# Interface_MCU.net
KiCad netlist of a schematic drawn in Altium Designer
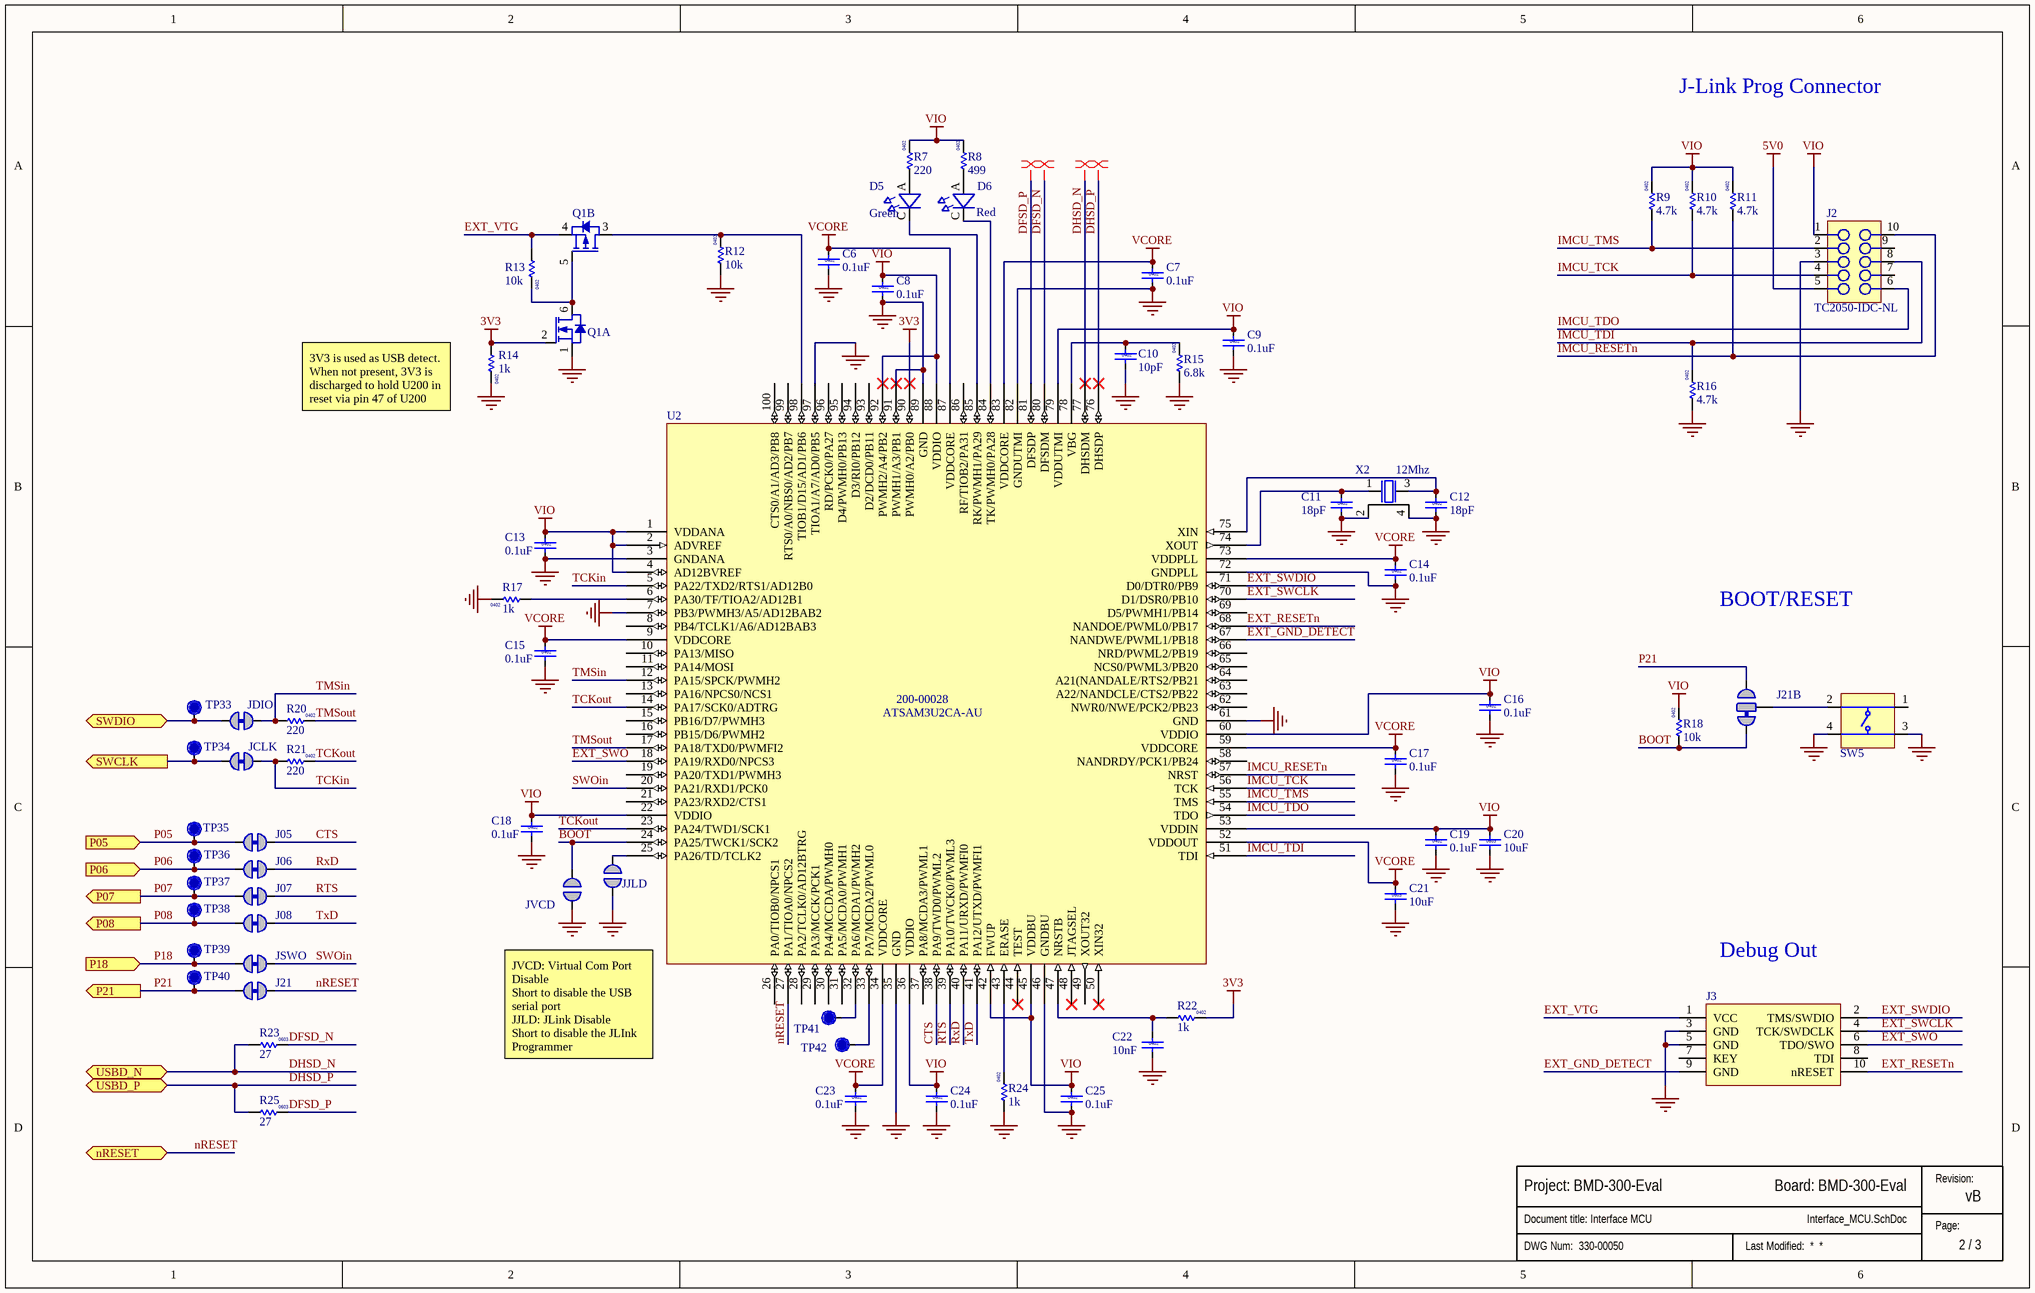
[diagram p0: Interface_MCU.SchDoc]

(export (version "E")
  (design (tool "Eeschema 10.0.6"))
  (components
    (comp (ref "C6")
      (value "0.1uF")
      (footprint "Cap 0402 HD")
      (description "Cap, Ceramic 0.1uF 10V 10% X5R 0402")
      (fields
        (field (name "SIZE") "0402")
        (field (name "PART NUMBER") "120-00016")
        (field (name "MANUFACTURER") "Murata Electronics North America")
      )
      (libsource (lib "Arena-Altium DB") (part "Cap Chip"))
    )
    (comp (ref "C7")
      (value "0.1uF")
      (footprint "Cap 0402 HD")
      (description "Cap, Ceramic 0.1uF 10V 10% X5R 0402")
      (fields
        (field (name "SIZE") "0402")
        (field (name "PART NUMBER") "120-00016")
        (field (name "MANUFACTURER") "Murata Electronics North America")
      )
      (libsource (lib "Arena-Altium DB") (part "Cap Chip"))
    )
    (comp (ref "C8")
      (value "0.1uF")
      (footprint "Cap 0402 HD")
      (description "Cap, Ceramic 0.1uF 10V 10% X5R 0402")
      (fields
        (field (name "SIZE") "0402")
        (field (name "PART NUMBER") "120-00016")
        (field (name "MANUFACTURER") "Murata Electronics North America")
      )
      (libsource (lib "Arena-Altium DB") (part "Cap Chip"))
    )
    (comp (ref "C9")
      (value "0.1uF")
      (footprint "Cap 0402 HD")
      (description "Cap, Ceramic 0.1uF 10V 10% X5R 0402")
      (fields
        (field (name "SIZE") "0402")
        (field (name "PART NUMBER") "120-00016")
        (field (name "MANUFACTURER") "Murata Electronics North America")
      )
      (libsource (lib "Arena-Altium DB") (part "Cap Chip"))
    )
    (comp (ref "C10")
      (value "10pF")
      (footprint "Cap 0402")
      (description "Cap, Ceramic, 10pF 50V 5% NPO 0402")
      (fields
        (field (name "SIZE") "0402")
        (field (name "PART NUMBER") "120-00065")
        (field (name "MANUFACTURER") "Murata Electronics North America")
      )
      (libsource (lib "Arena-Altium DB") (part "Cap Chip"))
    )
    (comp (ref "C11")
      (value "18pF")
      (footprint "Cap 0402 HD")
      (description "Cap, Ceramic 18pF 50V 5% NP0 0402")
      (fields
        (field (name "SIZE") "0402")
        (field (name "PART NUMBER") "120-00041")
        (field (name "MANUFACTURER") "Murata Electronics North America")
      )
      (libsource (lib "Arena-Altium DB") (part "Cap Chip"))
    )
    (comp (ref "C12")
      (value "18pF")
      (footprint "Cap 0402 HD")
      (description "Cap, Ceramic 18pF 50V 5% NP0 0402")
      (fields
        (field (name "SIZE") "0402")
        (field (name "PART NUMBER") "120-00041")
        (field (name "MANUFACTURER") "Murata Electronics North America")
      )
      (libsource (lib "Arena-Altium DB") (part "Cap Chip"))
    )
    (comp (ref "C13")
      (value "0.1uF")
      (footprint "Cap 0402 HD")
      (description "Cap, Ceramic 0.1uF 10V 10% X5R 0402")
      (fields
        (field (name "SIZE") "0402")
        (field (name "PART NUMBER") "120-00016")
        (field (name "MANUFACTURER") "Murata Electronics North America")
      )
      (libsource (lib "Arena-Altium DB") (part "Cap Chip"))
    )
    (comp (ref "C14")
      (value "0.1uF")
      (footprint "Cap 0402 HD")
      (description "Cap, Ceramic 0.1uF 10V 10% X5R 0402")
      (fields
        (field (name "SIZE") "0402")
        (field (name "PART NUMBER") "120-00016")
        (field (name "MANUFACTURER") "Murata Electronics North America")
      )
      (libsource (lib "Arena-Altium DB") (part "Cap Chip"))
    )
    (comp (ref "C15")
      (value "0.1uF")
      (footprint "Cap 0402 HD")
      (description "Cap, Ceramic 0.1uF 10V 10% X5R 0402")
      (fields
        (field (name "SIZE") "0402")
        (field (name "PART NUMBER") "120-00016")
        (field (name "MANUFACTURER") "Murata Electronics North America")
      )
      (libsource (lib "Arena-Altium DB") (part "Cap Chip"))
    )
    (comp (ref "C16")
      (value "0.1uF")
      (footprint "Cap 0402 HD")
      (description "Cap, Ceramic 0.1uF 10V 10% X5R 0402")
      (fields
        (field (name "SIZE") "0402")
        (field (name "PART NUMBER") "120-00016")
        (field (name "MANUFACTURER") "Murata Electronics North America")
      )
      (libsource (lib "Arena-Altium DB") (part "Cap Chip"))
    )
    (comp (ref "C17")
      (value "0.1uF")
      (footprint "Cap 0402 HD")
      (description "Cap, Ceramic 0.1uF 10V 10% X5R 0402")
      (fields
        (field (name "SIZE") "0402")
        (field (name "PART NUMBER") "120-00016")
        (field (name "MANUFACTURER") "Murata Electronics North America")
      )
      (libsource (lib "Arena-Altium DB") (part "Cap Chip"))
    )
    (comp (ref "C18")
      (value "0.1uF")
      (footprint "Cap 0402 HD")
      (description "Cap, Ceramic 0.1uF 10V 10% X5R 0402")
      (fields
        (field (name "SIZE") "0402")
        (field (name "PART NUMBER") "120-00016")
        (field (name "MANUFACTURER") "Murata Electronics North America")
      )
      (libsource (lib "Arena-Altium DB") (part "Cap Chip"))
    )
    (comp (ref "C19")
      (value "0.1uF")
      (footprint "Cap 0402 HD")
      (description "Cap, Ceramic 0.1uF 10V 10% X5R 0402")
      (fields
        (field (name "SIZE") "0402")
        (field (name "PART NUMBER") "120-00016")
        (field (name "MANUFACTURER") "Murata Electronics North America")
      )
      (libsource (lib "Arena-Altium DB") (part "Cap Chip"))
    )
    (comp (ref "C20")
      (value "10uF")
      (footprint "Cap 0603 HD")
      (description "Cap, Ceramic 10uF 10V 20% X5R 0603")
      (fields
        (field (name "SIZE") "0603")
        (field (name "PART NUMBER") "120-00024")
        (field (name "MANUFACTURER") "Murata Electronics North America")
      )
      (libsource (lib "Arena-Altium DB") (part "Cap Chip"))
    )
    (comp (ref "C21")
      (value "10uF")
      (footprint "Cap 0603 HD")
      (description "Cap, Ceramic 10uF 10V 20% X5R 0603")
      (fields
        (field (name "SIZE") "0603")
        (field (name "PART NUMBER") "120-00024")
        (field (name "MANUFACTURER") "Murata Electronics North America")
      )
      (libsource (lib "Arena-Altium DB") (part "Cap Chip"))
    )
    (comp (ref "C22")
      (value "10nF")
      (footprint "Cap 0402 HD")
      (description "CL05B103KO5NNNC")
      (fields
        (field (name "SIZE") "0402")
        (field (name "PART NUMBER") "120-00084")
        (field (name "MANUFACTURER") "Samsung Electro-Mechanics America, Inc")
      )
      (libsource (lib "Arena-Altium DB") (part "Cap Chip"))
    )
    (comp (ref "C23")
      (value "0.1uF")
      (footprint "Cap 0402 HD")
      (description "Cap, Ceramic 0.1uF 10V 10% X5R 0402")
      (fields
        (field (name "SIZE") "0402")
        (field (name "PART NUMBER") "120-00016")
        (field (name "MANUFACTURER") "Murata Electronics North America")
      )
      (libsource (lib "Arena-Altium DB") (part "Cap Chip"))
    )
    (comp (ref "C24")
      (value "0.1uF")
      (footprint "Cap 0402 HD")
      (description "Cap, Ceramic 0.1uF 10V 10% X5R 0402")
      (fields
        (field (name "SIZE") "0402")
        (field (name "PART NUMBER") "120-00016")
        (field (name "MANUFACTURER") "Murata Electronics North America")
      )
      (libsource (lib "Arena-Altium DB") (part "Cap Chip"))
    )
    (comp (ref "C25")
      (value "0.1uF")
      (footprint "Cap 0402 HD")
      (description "Cap, Ceramic 0.1uF 10V 10% X5R 0402")
      (fields
        (field (name "SIZE") "0402")
        (field (name "PART NUMBER") "120-00016")
        (field (name "MANUFACTURER") "Murata Electronics North America")
      )
      (libsource (lib "Arena-Altium DB") (part "Cap Chip"))
    )
    (comp (ref "D5")
      (value "115-00019")
      (footprint "Diode 0603 HD")
      (description "LED GREEN CLEAR 0603 SMD")
      (fields (field (name "COLOR") "Green") (field (name "MANUFACTURER") "Lite-On Inc"))
      (libsource (lib "Arena-Altium DB") (part "LED_BASE_AC"))
    )
    (comp (ref "D6")
      (value "115-00020")
      (footprint "Diode 0603 HD")
      (description "LED RED CLEAR 0603 SMD")
      (fields (field (name "COLOR") "Red") (field (name "MANUFACTURER") "Lite-On Inc"))
      (libsource (lib "Arena-Altium DB") (part "LED_BASE_AC"))
    )
    (comp (ref "J2")
      (value "TC2050-IDC-NLDNP")
      (footprint "TC2050-IDC-NL")
      (description "CON PADS FOR CBL PLUG-OF-NAILS 10-PIN NO LEGS")
      (fields
        (field (name "MANUFACTURER P/N") "TC2050-IDC-NL")
        (field (name "PART NUMBER") "TC2050-IDC-NL")
        (field (name "MANUFACTURER") "TAG Connect")
        (field (name "ADDED BY") "Paul B")
      )
      (libsource (lib "LEGACY_Rigado_AltiumLib") (part "CON-10Pin_2Row_ALT"))
    )
    (comp (ref "J3")
      (value "130-00099")
      (footprint "HDR.050P-10Pin-2x5-SMT_Key")
      (description "Header 0.05\" 10Pin 2Row SMD Black")
      (fields (field (name "MANUFACTURER") "Samtec"))
      (libsource (lib "Arena-Altium DB") (part "JTAG-10Pin"))
    )
    (comp (ref "J05")
      (value "Solderbridge-ShortDNP")
      (footprint "Solderbridge-Short")
      (description "Solderbridge-Short")
      (fields (field (name "ADDED BY") "Paul B"))
      (libsource (lib "LEGACY_Rigado_AltiumLib") (part "Solderbridge-Short"))
    )
    (comp (ref "J06")
      (value "Solderbridge-ShortDNP")
      (footprint "Solderbridge-Short")
      (description "Solderbridge-Short")
      (fields (field (name "ADDED BY") "Paul B"))
      (libsource (lib "LEGACY_Rigado_AltiumLib") (part "Solderbridge-Short"))
    )
    (comp (ref "J07")
      (value "Solderbridge-ShortDNP")
      (footprint "Solderbridge-Short")
      (description "Solderbridge-Short")
      (fields (field (name "ADDED BY") "Paul B"))
      (libsource (lib "LEGACY_Rigado_AltiumLib") (part "Solderbridge-Short"))
    )
    (comp (ref "J08")
      (value "Solderbridge-ShortDNP")
      (footprint "Solderbridge-Short")
      (description "Solderbridge-Short")
      (fields (field (name "ADDED BY") "Paul B"))
      (libsource (lib "LEGACY_Rigado_AltiumLib") (part "Solderbridge-Short"))
    )
    (comp (ref "J21")
      (value "Solderbridge-ShortDNP")
      (footprint "Solderbridge-Short")
      (description "Solderbridge-Short")
      (fields (field (name "ADDED BY") "Paul B"))
      (libsource (lib "LEGACY_Rigado_AltiumLib") (part "Solderbridge-Short"))
    )
    (comp (ref "J21B")
      (value "Solderbridge-OptionDNP")
      (footprint "Solderbridge-Option")
      (description "Solderbridge-Option")
      (fields (field (name "ADDED BY") "Paul B"))
      (libsource (lib "LEGACY_Rigado_AltiumLib") (part "Solderbridge-Option"))
    )
    (comp (ref "JCLK")
      (value "Solderbridge-ShortDNP")
      (footprint "Solderbridge-Short")
      (description "Solderbridge-Short")
      (fields (field (name "ADDED BY") "Paul B"))
      (libsource (lib "LEGACY_Rigado_AltiumLib") (part "Solderbridge-Short"))
    )
    (comp (ref "JDIO")
      (value "Solderbridge-ShortDNP")
      (footprint "Solderbridge-Short")
      (description "Solderbridge-Short")
      (fields (field (name "ADDED BY") "Paul B"))
      (libsource (lib "LEGACY_Rigado_AltiumLib") (part "Solderbridge-Short"))
    )
    (comp (ref "JJLD")
      (value "Solderbridge-OpenDNP")
      (footprint "Solderbridge-Open")
      (description "Solderbridge-Open")
      (fields (field (name "ADDED BY") "Paul B"))
      (libsource (lib "LEGACY_Rigado_AltiumLib") (part "Solderbridge-Open"))
    )
    (comp (ref "JSWO")
      (value "Solderbridge-ShortDNP")
      (footprint "Solderbridge-Short")
      (description "Solderbridge-Short")
      (fields (field (name "ADDED BY") "Paul B"))
      (libsource (lib "LEGACY_Rigado_AltiumLib") (part "Solderbridge-Short"))
    )
    (comp (ref "JVCD")
      (value "Solderbridge-OpenDNP")
      (footprint "Solderbridge-Open")
      (description "Solderbridge-Open")
      (fields (field (name "ADDED BY") "Paul B"))
      (libsource (lib "LEGACY_Rigado_AltiumLib") (part "Solderbridge-Open"))
    )
    (comp (ref "Q1")
      (value "140-00019")
      (footprint "SOT-963")
      (description "Mosfet, Dual, N-Channel and P-Channel Pair, 20V 180mA, SOT963")
      (fields (field (name "MANUFACTURER") "Diodes Incorporated") (field (name "VOLTAGE") "20V, -20V"))
      (libsource (lib "Arena-Altium DB") (part "MOSFET-N-P_Pair"))
    )
    (comp (ref "R7")
      (value "220")
      (footprint "RES 0402 HD")
      (description "RC1005J221CS")
      (fields
        (field (name "SIZE") "0402")
        (field (name "PART NUMBER") "180-00098")
        (field (name "MANUFACTURER") "Samsung Electro-Mechanics America, Inc")
      )
      (libsource (lib "Arena-Altium DB") (part "Res sm"))
    )
    (comp (ref "R8")
      (value "499")
      (footprint "RES 0402 HD")
      (description "Resistor 499 ohm 1%, 1/16W, 0402")
      (fields
        (field (name "SIZE") "0402")
        (field (name "PART NUMBER") "180-00031")
        (field (name "MANUFACTURER") "Rohm Semiconductor")
      )
      (libsource (lib "Arena-Altium DB") (part "Res sm"))
    )
    (comp (ref "R9")
      (value "4.7k")
      (footprint "RES 0402 HD")
      (description "RES SMD 4.7K OHM 1% 1/16W 0402")
      (fields
        (field (name "SIZE") "0402")
        (field (name "PART NUMBER") "180-00121")
        (field (name "MANUFACTURER") "Samsung Electro-Mechanics America, Inc")
      )
      (libsource (lib "Arena-Altium DB") (part "Res sm"))
    )
    (comp (ref "R10")
      (value "4.7k")
      (footprint "RES 0402 HD")
      (description "RES SMD 4.7K OHM 1% 1/16W 0402")
      (fields
        (field (name "SIZE") "0402")
        (field (name "PART NUMBER") "180-00121")
        (field (name "MANUFACTURER") "Samsung Electro-Mechanics America, Inc")
      )
      (libsource (lib "Arena-Altium DB") (part "Res sm"))
    )
    (comp (ref "R11")
      (value "4.7k")
      (footprint "RES 0402 HD")
      (description "RES SMD 4.7K OHM 1% 1/16W 0402")
      (fields
        (field (name "SIZE") "0402")
        (field (name "PART NUMBER") "180-00121")
        (field (name "MANUFACTURER") "Samsung Electro-Mechanics America, Inc")
      )
      (libsource (lib "Arena-Altium DB") (part "Res sm"))
    )
    (comp (ref "R12")
      (value "10k")
      (footprint "RES 0402 HD")
      (description "Resistor 10k ohm 1% 1/16W, 0402")
      (fields
        (field (name "SIZE") "0402")
        (field (name "PART NUMBER") "180-00024")
        (field (name "MANUFACTURER") "Rohm Semiconductor")
      )
      (libsource (lib "Arena-Altium DB") (part "Res sm"))
    )
    (comp (ref "R13")
      (value "10k")
      (footprint "RES 0402 HD")
      (description "Resistor 10k ohm 1% 1/16W, 0402")
      (fields
        (field (name "SIZE") "0402")
        (field (name "PART NUMBER") "180-00024")
        (field (name "MANUFACTURER") "Rohm Semiconductor")
      )
      (libsource (lib "Arena-Altium DB") (part "Res sm"))
    )
    (comp (ref "R14")
      (value "1k")
      (footprint "RES 0402 HD")
      (description "Resistor 1k ohm 1% 1/16W, 0402")
      (fields
        (field (name "SIZE") "0402")
        (field (name "PART NUMBER") "180-00021")
        (field (name "MANUFACTURER") "Rohm Semiconductor")
      )
      (libsource (lib "Arena-Altium DB") (part "Res sm"))
    )
    (comp (ref "R15")
      (value "6.8k")
      (footprint "RES 0402")
      (description "Resistor 6.8k ohm 1%, 1/16W, 0402")
      (fields
        (field (name "SIZE") "0402")
        (field (name "PART NUMBER") "180-00068")
        (field (name "MANUFACTURER") "Rohm Semiconductor")
      )
      (libsource (lib "Arena-Altium DB") (part "Res sm"))
    )
    (comp (ref "R16")
      (value "4.7k")
      (footprint "RES 0402 HD")
      (description "RES SMD 4.7K OHM 1% 1/16W 0402")
      (fields
        (field (name "SIZE") "0402")
        (field (name "PART NUMBER") "180-00121")
        (field (name "MANUFACTURER") "Samsung Electro-Mechanics America, Inc")
      )
      (libsource (lib "Arena-Altium DB") (part "Res sm"))
    )
    (comp (ref "R17")
      (value "1k")
      (footprint "RES 0402 HD")
      (description "Resistor 1k ohm 1% 1/16W, 0402")
      (fields
        (field (name "SIZE") "0402")
        (field (name "PART NUMBER") "180-00021")
        (field (name "MANUFACTURER") "Rohm Semiconductor")
      )
      (libsource (lib "Arena-Altium DB") (part "Res sm"))
    )
    (comp (ref "R18")
      (value "10k")
      (footprint "RES 0402 HD")
      (description "Resistor 10k ohm 1% 1/16W, 0402")
      (fields
        (field (name "SIZE") "0402")
        (field (name "PART NUMBER") "180-00024")
        (field (name "MANUFACTURER") "Rohm Semiconductor")
      )
      (libsource (lib "Arena-Altium DB") (part "Res sm"))
    )
    (comp (ref "R20")
      (value "220")
      (footprint "RES 0402 HD")
      (description "Resistor 220 ohm 1%, 1/16W, 0402")
      (fields
        (field (name "SIZE") "0402")
        (field (name "PART NUMBER") "180-00056")
        (field (name "MANUFACTURER") "Panasonic Electronic Components")
      )
      (libsource (lib "Arena-Altium DB") (part "Res sm"))
    )
    (comp (ref "R21")
      (value "220")
      (footprint "RES 0402 HD")
      (description "Resistor 220 ohm 1%, 1/16W, 0402")
      (fields
        (field (name "SIZE") "0402")
        (field (name "PART NUMBER") "180-00056")
        (field (name "MANUFACTURER") "Panasonic Electronic Components")
      )
      (libsource (lib "Arena-Altium DB") (part "Res sm"))
    )
    (comp (ref "R22")
      (value "1k")
      (footprint "RES 0402 HD")
      (description "Resistor 1k ohm 1% 1/16W, 0402")
      (fields
        (field (name "SIZE") "0402")
        (field (name "PART NUMBER") "180-00021")
        (field (name "MANUFACTURER") "Rohm Semiconductor")
      )
      (libsource (lib "Arena-Altium DB") (part "Res sm"))
    )
    (comp (ref "R23")
      (value "27")
      (footprint "RES 0603 HD")
      (description "Resistor 27 ohm 5%, 1/10W, 0603")
      (fields
        (field (name "SIZE") "0603")
        (field (name "PART NUMBER") "180-00006")
        (field (name "MANUFACTURER") "Rohm Semiconductor")
      )
      (libsource (lib "Arena-Altium DB") (part "Res sm"))
    )
    (comp (ref "R24")
      (value "1k")
      (footprint "RES 0402 HD")
      (description "Resistor 1k ohm 1% 1/16W, 0402")
      (fields
        (field (name "SIZE") "0402")
        (field (name "PART NUMBER") "180-00021")
        (field (name "MANUFACTURER") "Rohm Semiconductor")
      )
      (libsource (lib "Arena-Altium DB") (part "Res sm"))
    )
    (comp (ref "R25")
      (value "27")
      (footprint "RES 0603 HD")
      (description "Resistor 27 ohm 5%, 1/10W, 0603")
      (fields
        (field (name "SIZE") "0603")
        (field (name "PART NUMBER") "180-00006")
        (field (name "MANUFACTURER") "Rohm Semiconductor")
      )
      (libsource (lib "Arena-Altium DB") (part "Res sm"))
    )
    (comp (ref "SW5")
      (value "135-00002")
      (footprint "SW_TACT_SMT_6mm")
      (description "Tactile Switch, SPST-NO, SMT 160gf.")
      (fields (field (name "MANUFACTURER") "C&K Components") (field (name "VOLTAGE") "12VDC"))
      (libsource (lib "Arena-Altium DB") (part "SW_TACT_SPST_4Pin"))
    )
    (comp (ref "TP33")
      (value "TP")
      (footprint "TP10R")
      (description "Testpoint, Round 1.0mm Dia")
      (fields
        (field (name "PART NUMBER") "TP10R")
        (field (name "ADDED BY") "Jeremy D")
        (field (name "CHECKED BY") "Paul B")
      )
      (libsource (lib "LEGACY_Rigado_AltiumLib") (part "TP_R"))
    )
    (comp (ref "TP34")
      (value "TP")
      (footprint "TP10R")
      (description "Testpoint, Round 1.0mm Dia")
      (fields
        (field (name "PART NUMBER") "TP10R")
        (field (name "ADDED BY") "Jeremy D")
        (field (name "CHECKED BY") "Paul B")
      )
      (libsource (lib "LEGACY_Rigado_AltiumLib") (part "TP_R"))
    )
    (comp (ref "TP35")
      (value "TP")
      (footprint "TP10R")
      (description "Testpoint, Round 1.0mm Dia")
      (fields
        (field (name "PART NUMBER") "TP10R")
        (field (name "ADDED BY") "Jeremy D")
        (field (name "CHECKED BY") "Paul B")
      )
      (libsource (lib "LEGACY_Rigado_AltiumLib") (part "TP_R"))
    )
    (comp (ref "TP36")
      (value "TP")
      (footprint "TP10R")
      (description "Testpoint, Round 1.0mm Dia")
      (fields
        (field (name "PART NUMBER") "TP10R")
        (field (name "ADDED BY") "Jeremy D")
        (field (name "CHECKED BY") "Paul B")
      )
      (libsource (lib "LEGACY_Rigado_AltiumLib") (part "TP_R"))
    )
    (comp (ref "TP37")
      (value "TP")
      (footprint "TP10R")
      (description "Testpoint, Round 1.0mm Dia")
      (fields
        (field (name "PART NUMBER") "TP10R")
        (field (name "ADDED BY") "Jeremy D")
        (field (name "CHECKED BY") "Paul B")
      )
      (libsource (lib "LEGACY_Rigado_AltiumLib") (part "TP_R"))
    )
    (comp (ref "TP38")
      (value "TP")
      (footprint "TP10R")
      (description "Testpoint, Round 1.0mm Dia")
      (fields
        (field (name "PART NUMBER") "TP10R")
        (field (name "ADDED BY") "Jeremy D")
        (field (name "CHECKED BY") "Paul B")
      )
      (libsource (lib "LEGACY_Rigado_AltiumLib") (part "TP_R"))
    )
    (comp (ref "TP39")
      (value "TP")
      (footprint "TP10R")
      (description "Testpoint, Round 1.0mm Dia")
      (fields
        (field (name "PART NUMBER") "TP10R")
        (field (name "ADDED BY") "Jeremy D")
        (field (name "CHECKED BY") "Paul B")
      )
      (libsource (lib "LEGACY_Rigado_AltiumLib") (part "TP_R"))
    )
    (comp (ref "TP40")
      (value "TP")
      (footprint "TP10R")
      (description "Testpoint, Round 1.0mm Dia")
      (fields
        (field (name "PART NUMBER") "TP10R")
        (field (name "ADDED BY") "Jeremy D")
        (field (name "CHECKED BY") "Paul B")
      )
      (libsource (lib "LEGACY_Rigado_AltiumLib") (part "TP_R"))
    )
    (comp (ref "TP41")
      (value "TP")
      (footprint "TP10R")
      (description "Testpoint, Round 1.0mm Dia")
      (fields
        (field (name "PART NUMBER") "TP10R")
        (field (name "ADDED BY") "Jeremy D")
        (field (name "CHECKED BY") "Paul B")
      )
      (libsource (lib "LEGACY_Rigado_AltiumLib") (part "TP_R"))
    )
    (comp (ref "TP42")
      (value "TP")
      (footprint "TP10R")
      (description "Testpoint, Round 1.0mm Dia")
      (fields
        (field (name "PART NUMBER") "TP10R")
        (field (name "ADDED BY") "Jeremy D")
        (field (name "CHECKED BY") "Paul B")
      )
      (libsource (lib "LEGACY_Rigado_AltiumLib") (part "TP_R"))
    )
    (comp (ref "U2")
      (value "200-00028")
      (footprint "QFP0.5P25x25-100Pin")
      (description "IC MCU 32BIT 128KB FLASH 100LQFP")
      (fields
        (field (name "MANUFACTURER P/N") "ATSAM3U2CA-AU")
        (field (name "MANUFACTURER") "Atmel")
        (field (name "VOLTAGE") "3.6V")
      )
      (libsource (lib "Arena-Altium DB") (part "ATSAM3UxCA-AU"))
    )
    (comp (ref "X2")
      (value "100-00013")
      (footprint "XTAL_3225")
      (description "7M-12.000MAAJ-T")
      (fields (field (name "FREQUENCY") "12Mhz") (field (name "MANUFACTURER") "TXC CORPORATION"))
      (libsource (lib "Arena-Altium DB") (part "XTAL_4Pin"))
    )
  )
  (nets
    (net (code "1") (name "/BOOT") (class "Default")
      (node (ref "J21B") (pin "1") (pinfunction "1_1") (pintype "passive"))
      (node (ref "JVCD") (pin "2") (pinfunction "2_2") (pintype "passive"))
      (node (ref "R18") (pin "1") (pinfunction "1_1") (pintype "passive"))
      (node (ref "U2") (pin "24") (pinfunction "PA25/TWCK1/SCK2_24") (pintype "bidirectional"))
    )
    (net (code "2") (name "/CTS") (class "Default")
      (node (ref "J05") (pin "1") (pinfunction "1_1") (pintype "passive"))
      (node (ref "U2") (pin "38") (pinfunction "PA9/TWD0/PWML2_38") (pintype "bidirectional"))
    )
    (net (code "3") (name "/DFSD_N") (class "Default")
      (node (ref "R23") (pin "2") (pinfunction "2_2") (pintype "passive"))
      (node (ref "U2") (pin "80") (pinfunction "DFSDM_80") (pintype "bidirectional"))
    )
    (net (code "4") (name "/DFSD_P") (class "Default")
      (node (ref "R25") (pin "2") (pinfunction "2_2") (pintype "passive"))
      (node (ref "U2") (pin "81") (pinfunction "DFSDP_81") (pintype "bidirectional"))
    )
    (net (code "5") (name "/DHSD_N") (class "Default")
      (node (ref "R23") (pin "1") (pinfunction "1_1") (pintype "passive"))
      (node (ref "U2") (pin "77") (pinfunction "DHSDM_77") (pintype "bidirectional"))
    )
    (net (code "6") (name "/DHSD_P") (class "Default")
      (node (ref "R25") (pin "1") (pinfunction "1_1") (pintype "passive"))
      (node (ref "U2") (pin "76") (pinfunction "DHSDP_76") (pintype "bidirectional"))
    )
    (net (code "7") (name "/EXT_GND_DETECT") (class "Default")
      (node (ref "J3") (pin "9") (pinfunction "GND_9") (pintype "passive"))
      (node (ref "U2") (pin "67") (pinfunction "NANDWE/PWML1/PB18_67") (pintype "bidirectional"))
    )
    (net (code "8") (name "/EXT_RESETn") (class "Default")
      (node (ref "J3") (pin "10") (pinfunction "nRESET_10") (pintype "passive"))
      (node (ref "U2") (pin "68") (pinfunction "NANDOE/PWML0/PB17_68") (pintype "bidirectional"))
    )
    (net (code "9") (name "/EXT_SWCLK") (class "Default")
      (node (ref "J3") (pin "4") (pinfunction "TCK/SWDCLK_4") (pintype "passive"))
      (node (ref "U2") (pin "70") (pinfunction "D1/DSR0/PB10_70") (pintype "bidirectional"))
    )
    (net (code "10") (name "/EXT_SWDIO") (class "Default")
      (node (ref "J3") (pin "2") (pinfunction "TMS/SWDIO_2") (pintype "passive"))
      (node (ref "U2") (pin "71") (pinfunction "D0/DTR0/PB9_71") (pintype "bidirectional"))
    )
    (net (code "11") (name "/EXT_SWO") (class "Default")
      (node (ref "J3") (pin "6") (pinfunction "TDO/SWO_6") (pintype "passive"))
      (node (ref "U2") (pin "18") (pinfunction "PA19/RXD0/NPCS3_18") (pintype "bidirectional"))
    )
    (net (code "12") (name "/EXT_VTG") (class "Default")
      (node (ref "J3") (pin "1") (pinfunction "VCC_1") (pintype "passive"))
      (node (ref "Q1") (pin "4") (pinfunction "S2_4") (pintype "passive"))
      (node (ref "R13") (pin "1") (pinfunction "1_1") (pintype "passive"))
    )
    (net (code "13") (name "/IMCU_RESETn") (class "Default")
      (node (ref "J2") (pin "10") (pintype "passive"))
      (node (ref "R11") (pin "1") (pinfunction "1_1") (pintype "passive"))
      (node (ref "U2") (pin "57") (pinfunction "NRST_57") (pintype "bidirectional"))
    )
    (net (code "14") (name "/IMCU_TCK") (class "Default")
      (node (ref "J2") (pin "4") (pintype "passive"))
      (node (ref "R10") (pin "1") (pinfunction "1_1") (pintype "passive"))
      (node (ref "U2") (pin "56") (pinfunction "TCK_56") (pintype "input"))
    )
    (net (code "15") (name "/IMCU_TDI") (class "Default")
      (node (ref "J2") (pin "8") (pintype "passive"))
      (node (ref "R16") (pin "2") (pinfunction "2_2") (pintype "passive"))
      (node (ref "U2") (pin "51") (pinfunction "TDI_51") (pintype "input"))
    )
    (net (code "16") (name "/IMCU_TDO") (class "Default")
      (node (ref "J2") (pin "6") (pintype "passive"))
      (node (ref "U2") (pin "54") (pinfunction "TDO_54") (pintype "output"))
    )
    (net (code "17") (name "/IMCU_TMS") (class "Default")
      (node (ref "J2") (pin "2") (pintype "passive"))
      (node (ref "R9") (pin "1") (pinfunction "1_1") (pintype "passive"))
      (node (ref "U2") (pin "55") (pinfunction "TMS_55") (pintype "input"))
    )
    (net (code "18") (name "/P05") (class "Default")
      (node (ref "J05") (pin "2") (pinfunction "2_2") (pintype "passive"))
      (node (ref "TP35") (pin "1") (pintype "passive"))
    )
    (net (code "19") (name "/P06") (class "Default")
      (node (ref "J06") (pin "2") (pinfunction "2_2") (pintype "passive"))
      (node (ref "TP36") (pin "1") (pintype "passive"))
    )
    (net (code "20") (name "/P07") (class "Default")
      (node (ref "J07") (pin "2") (pinfunction "2_2") (pintype "passive"))
      (node (ref "TP37") (pin "1") (pintype "passive"))
    )
    (net (code "21") (name "/P08") (class "Default")
      (node (ref "J08") (pin "2") (pinfunction "2_2") (pintype "passive"))
      (node (ref "TP38") (pin "1") (pintype "passive"))
    )
    (net (code "22") (name "/P18") (class "Default")
      (node (ref "JSWO") (pin "2") (pinfunction "2_2") (pintype "passive"))
      (node (ref "TP39") (pin "1") (pintype "passive"))
    )
    (net (code "23") (name "/P21") (class "Default")
      (node (ref "J21") (pin "2") (pinfunction "2_2") (pintype "passive"))
      (node (ref "J21B") (pin "3") (pinfunction "3_3") (pintype "passive"))
      (node (ref "TP40") (pin "1") (pintype "passive"))
    )
    (net (code "24") (name "/RTS") (class "Default")
      (node (ref "J07") (pin "1") (pinfunction "1_1") (pintype "passive"))
      (node (ref "U2") (pin "39") (pinfunction "PA10/TWCK0/PWML3_39") (pintype "bidirectional"))
    )
    (net (code "25") (name "/RxD") (class "Default")
      (node (ref "J06") (pin "1") (pinfunction "1_1") (pintype "passive"))
      (node (ref "U2") (pin "40") (pinfunction "PA11/URXD/PWMFI0_40") (pintype "bidirectional"))
    )
    (net (code "26") (name "/SWCLK") (class "Default")
      (node (ref "JCLK") (pin "2") (pinfunction "2_2") (pintype "passive"))
      (node (ref "TP34") (pin "1") (pintype "passive"))
    )
    (net (code "27") (name "/SWDIO") (class "Default")
      (node (ref "JDIO") (pin "2") (pinfunction "2_2") (pintype "passive"))
      (node (ref "TP33") (pin "1") (pintype "passive"))
    )
    (net (code "28") (name "/SWOin") (class "Default")
      (node (ref "JSWO") (pin "1") (pinfunction "1_1") (pintype "passive"))
      (node (ref "U2") (pin "20") (pinfunction "PA21/RXD1/PCK0_20") (pintype "bidirectional"))
    )
    (net (code "29") (name "/TCKin") (class "Default")
      (node (ref "JCLK") (pin "1") (pinfunction "1_1") (pintype "passive"))
      (node (ref "R21") (pin "1") (pinfunction "1_1") (pintype "passive"))
      (node (ref "U2") (pin "5") (pinfunction "PA22/TXD2/RTS1/AD12B0_5") (pintype "bidirectional"))
    )
    (net (code "30") (name "/TCKout") (class "Default")
      (node (ref "R21") (pin "2") (pinfunction "2_2") (pintype "passive"))
      (node (ref "U2") (pin "14") (pinfunction "PA17/SCK0/ADTRG_14") (pintype "bidirectional"))
      (node (ref "U2") (pin "23") (pinfunction "PA24/TWD1/SCK1_23") (pintype "bidirectional"))
    )
    (net (code "31") (name "/TMSin") (class "Default")
      (node (ref "JDIO") (pin "1") (pinfunction "1_1") (pintype "passive"))
      (node (ref "R20") (pin "1") (pinfunction "1_1") (pintype "passive"))
      (node (ref "U2") (pin "12") (pinfunction "PA15/SPCK/PWMH2_12") (pintype "bidirectional"))
    )
    (net (code "32") (name "/TMSout") (class "Default")
      (node (ref "R20") (pin "2") (pinfunction "2_2") (pintype "passive"))
      (node (ref "U2") (pin "17") (pinfunction "PA18/TXD0/PWMFI2_17") (pintype "bidirectional"))
    )
    (net (code "33") (name "/TxD") (class "Default")
      (node (ref "J08") (pin "1") (pinfunction "1_1") (pintype "passive"))
      (node (ref "U2") (pin "41") (pinfunction "PA12/UTXD/PWMFI1_41") (pintype "bidirectional"))
    )
    (net (code "34") (name "/nRESET") (class "Default")
      (node (ref "J21") (pin "1") (pinfunction "1_1") (pintype "passive"))
      (node (ref "U2") (pin "27") (pinfunction "PA1/TIOA0/NPCS2_27") (pintype "bidirectional"))
    )
    (net (code "35") (name "3V3") (class "Default")
      (node (ref "Q1") (pin "2") (pinfunction "G1_2") (pintype "passive"))
      (node (ref "R14") (pin "1") (pinfunction "1_1") (pintype "passive"))
      (node (ref "R22") (pin "2") (pinfunction "2_2") (pintype "passive"))
      (node (ref "U2") (pin "90") (pinfunction "PWMH0/A2/PB0_90") (pintype "bidirectional"))
    )
    (net (code "36") (name "5V0") (class "Default") (node (ref "J2") (pin "5") (pintype "passive")))
    (net (code "37") (name "GND") (class "Default")
      (node (ref "C10") (pin "2") (pinfunction "2_2") (pintype "passive"))
      (node (ref "C11") (pin "2") (pinfunction "2_2") (pintype "passive"))
      (node (ref "C12") (pin "2") (pinfunction "2_2") (pintype "passive"))
      (node (ref "C13") (pin "2") (pinfunction "2_2") (pintype "passive"))
      (node (ref "C14") (pin "2") (pinfunction "2_2") (pintype "passive"))
      (node (ref "C15") (pin "2") (pinfunction "2_2") (pintype "passive"))
      (node (ref "C16") (pin "2") (pinfunction "2_2") (pintype "passive"))
      (node (ref "C17") (pin "2") (pinfunction "2_2") (pintype "passive"))
      (node (ref "C18") (pin "2") (pinfunction "2_2") (pintype "passive"))
      (node (ref "C19") (pin "2") (pinfunction "2_2") (pintype "passive"))
      (node (ref "C20") (pin "2") (pinfunction "2_2") (pintype "passive"))
      (node (ref "C21") (pin "2") (pinfunction "2_2") (pintype "passive"))
      (node (ref "C22") (pin "2") (pinfunction "2_2") (pintype "passive"))
      (node (ref "C23") (pin "2") (pinfunction "2_2") (pintype "passive"))
      (node (ref "C24") (pin "2") (pinfunction "2_2") (pintype "passive"))
      (node (ref "C25") (pin "2") (pinfunction "2_2") (pintype "passive"))
      (node (ref "C6") (pin "2") (pinfunction "2_2") (pintype "passive"))
      (node (ref "C7") (pin "2") (pinfunction "2_2") (pintype "passive"))
      (node (ref "C8") (pin "2") (pinfunction "2_2") (pintype "passive"))
      (node (ref "C9") (pin "2") (pinfunction "2_2") (pintype "passive"))
      (node (ref "J2") (pin "3") (pintype "passive"))
      (node (ref "J3") (pin "3") (pinfunction "GND_3") (pintype "passive"))
      (node (ref "J3") (pin "5") (pinfunction "GND_5") (pintype "passive"))
      (node (ref "JJLD") (pin "1") (pinfunction "1_1") (pintype "passive"))
      (node (ref "JVCD") (pin "1") (pinfunction "1_1") (pintype "passive"))
      (node (ref "Q1") (pin "1") (pinfunction "S1_1") (pintype "passive"))
      (node (ref "R12") (pin "1") (pinfunction "1_1") (pintype "passive"))
      (node (ref "R14") (pin "2") (pinfunction "2_2") (pintype "passive"))
      (node (ref "R15") (pin "1") (pinfunction "1_1") (pintype "passive"))
      (node (ref "R16") (pin "1") (pinfunction "1_1") (pintype "passive"))
      (node (ref "R17") (pin "2") (pinfunction "2_2") (pintype "passive"))
      (node (ref "R24") (pin "1") (pinfunction "1_1") (pintype "passive"))
      (node (ref "SW5") (pin "3") (pinfunction "T3_3") (pintype "passive"))
      (node (ref "SW5") (pin "4") (pinfunction "T3_4") (pintype "passive"))
      (node (ref "U2") (pin "3") (pinfunction "GNDANA_3") (pintype "power_in"))
      (node (ref "U2") (pin "35") (pinfunction "GND_35") (pintype "power_in"))
      (node (ref "U2") (pin "46") (pinfunction "GNDBU_46") (pintype "power_in"))
      (node (ref "U2") (pin "61") (pinfunction "GND_61") (pintype "power_in"))
      (node (ref "U2") (pin "7") (pinfunction "PB3/PWMH3/A5/AD12BAB2_7") (pintype "bidirectional"))
      (node (ref "U2") (pin "72") (pinfunction "GNDPLL_72") (pintype "power_in"))
      (node (ref "U2") (pin "82") (pinfunction "GNDUTMI_82") (pintype "power_in"))
      (node (ref "U2") (pin "89") (pinfunction "GND_89") (pintype "power_in"))
      (node (ref "U2") (pin "91") (pinfunction "PWMH1/A3/PB1_91") (pintype "bidirectional"))
      (node (ref "U2") (pin "97") (pinfunction "TIOA1/A7/AD0/PB5_97") (pintype "bidirectional"))
      (node (ref "X2") (pin "2") (pintype "passive"))
      (node (ref "X2") (pin "4") (pintype "passive"))
    )
    (net (code "38") (name "Net-(D5-Anode)") (class "Default")
      (node (ref "D5") (pin "A") (pinfunction "Anode_A") (pintype "passive"))
      (node (ref "R7") (pin "1") (pinfunction "1_1") (pintype "passive"))
    )
    (net (code "39") (name "Net-(D5-Cathode)") (class "Default")
      (node (ref "D5") (pin "C") (pinfunction "Cathode_C") (pintype "passive"))
      (node (ref "U2") (pin "85") (pinfunction "RK/PWMH1/PA29_85") (pintype "bidirectional"))
    )
    (net (code "40") (name "Net-(D6-Anode)") (class "Default")
      (node (ref "D6") (pin "A") (pinfunction "Anode_A") (pintype "passive"))
      (node (ref "R8") (pin "1") (pinfunction "1_1") (pintype "passive"))
    )
    (net (code "41") (name "Net-(D6-Cathode)") (class "Default")
      (node (ref "D6") (pin "C") (pinfunction "Cathode_C") (pintype "passive"))
      (node (ref "U2") (pin "84") (pinfunction "TK/PWMH0/PA28_84") (pintype "bidirectional"))
    )
    (net (code "42") (name "Net-(Q1A-D1)") (class "Default")
      (node (ref "Q1") (pin "5") (pinfunction "G2_5") (pintype "passive"))
      (node (ref "Q1") (pin "6") (pinfunction "D1_6") (pintype "passive"))
      (node (ref "R13") (pin "2") (pinfunction "2_2") (pintype "passive"))
    )
    (net (code "43") (name "Net-(Q1B-D2)") (class "Default")
      (node (ref "Q1") (pin "3") (pinfunction "D2_3") (pintype "passive"))
      (node (ref "R12") (pin "2") (pinfunction "2_2") (pintype "passive"))
      (node (ref "U2") (pin "98") (pinfunction "TIOB1/D15/AD1/PB6_98") (pintype "bidirectional"))
    )
    (net (code "44") (name "Net-(SW5-T2)") (class "Default")
      (node (ref "J21B") (pin "2") (pinfunction "2_2") (pintype "passive"))
      (node (ref "SW5") (pin "2") (pinfunction "T2_2") (pintype "passive"))
    )
    (net (code "45") (name "Net-(U2-ERASE)") (class "Default")
      (node (ref "R24") (pin "2") (pinfunction "2_2") (pintype "passive"))
      (node (ref "U2") (pin "43") (pinfunction "ERASE_43") (pintype "input"))
    )
    (net (code "46") (name "Net-(U2-NRSTB)") (class "Default")
      (node (ref "C22") (pin "1") (pinfunction "1_1") (pintype "passive"))
      (node (ref "R22") (pin "1") (pinfunction "1_1") (pintype "passive"))
      (node (ref "U2") (pin "47") (pinfunction "NRSTB_47") (pintype "input"))
    )
    (net (code "47") (name "Net-(U2-PA6{slash}MCDA1{slash}PWMH2)") (class "Default")
      (node (ref "TP41") (pin "1") (pintype "passive"))
      (node (ref "U2") (pin "32") (pinfunction "PA6/MCDA1/PWMH2_32") (pintype "bidirectional"))
    )
    (net (code "48") (name "Net-(U2-PA7{slash}MCDA2{slash}PWML0)") (class "Default")
      (node (ref "TP42") (pin "1") (pintype "passive"))
      (node (ref "U2") (pin "33") (pinfunction "PA7/MCDA2/PWML0_33") (pintype "bidirectional"))
    )
    (net (code "49") (name "Net-(U2-PA26{slash}TD{slash}TCLK2)") (class "Default")
      (node (ref "JJLD") (pin "2") (pinfunction "2_2") (pintype "passive"))
      (node (ref "U2") (pin "25") (pinfunction "PA26/TD/TCLK2_25") (pintype "bidirectional"))
    )
    (net (code "50") (name "Net-(U2-PA30{slash}TF{slash}TIOA2{slash}AD12B1)") (class "Default")
      (node (ref "R17") (pin "1") (pinfunction "1_1") (pintype "passive"))
      (node (ref "U2") (pin "6") (pinfunction "PA30/TF/TIOA2/AD12B1_6") (pintype "bidirectional"))
    )
    (net (code "51") (name "Net-(U2-VBG)") (class "Default")
      (node (ref "C10") (pin "1") (pinfunction "1_1") (pintype "passive"))
      (node (ref "R15") (pin "2") (pinfunction "2_2") (pintype "passive"))
      (node (ref "U2") (pin "78") (pinfunction "VBG_78") (pintype "power_in"))
    )
    (net (code "52") (name "Net-(U2-XIN)") (class "Default")
      (node (ref "C12") (pin "1") (pinfunction "1_1") (pintype "passive"))
      (node (ref "U2") (pin "75") (pinfunction "XIN_75") (pintype "input"))
      (node (ref "X2") (pin "3") (pintype "passive"))
    )
    (net (code "53") (name "Net-(U2-XOUT)") (class "Default")
      (node (ref "C11") (pin "1") (pinfunction "1_1") (pintype "passive"))
      (node (ref "U2") (pin "74") (pinfunction "XOUT_74") (pintype "output"))
      (node (ref "X2") (pin "1") (pintype "passive"))
    )
    (net (code "54") (name "VCORE") (class "Default")
      (node (ref "C14") (pin "1") (pinfunction "1_1") (pintype "passive"))
      (node (ref "C15") (pin "1") (pinfunction "1_1") (pintype "passive"))
      (node (ref "C17") (pin "1") (pinfunction "1_1") (pintype "passive"))
      (node (ref "C21") (pin "1") (pinfunction "1_1") (pintype "passive"))
      (node (ref "C23") (pin "1") (pinfunction "1_1") (pintype "passive"))
      (node (ref "C6") (pin "1") (pinfunction "1_1") (pintype "passive"))
      (node (ref "C7") (pin "1") (pinfunction "1_1") (pintype "passive"))
      (node (ref "U2") (pin "34") (pinfunction "VDDCORE_34") (pintype "power_in"))
      (node (ref "U2") (pin "52") (pinfunction "VDDOUT_52") (pintype "power_in"))
      (node (ref "U2") (pin "59") (pinfunction "VDDCORE_59") (pintype "power_in"))
      (node (ref "U2") (pin "73") (pinfunction "VDDPLL_73") (pintype "power_in"))
      (node (ref "U2") (pin "83") (pinfunction "VDDCORE_83") (pintype "power_in"))
      (node (ref "U2") (pin "87") (pinfunction "VDDCORE_87") (pintype "power_in"))
      (node (ref "U2") (pin "9") (pinfunction "VDDCORE_9") (pintype "power_in"))
    )
    (net (code "55") (name "VIO") (class "Default")
      (node (ref "C13") (pin "1") (pinfunction "1_1") (pintype "passive"))
      (node (ref "C16") (pin "1") (pinfunction "1_1") (pintype "passive"))
      (node (ref "C18") (pin "1") (pinfunction "1_1") (pintype "passive"))
      (node (ref "C19") (pin "1") (pinfunction "1_1") (pintype "passive"))
      (node (ref "C20") (pin "1") (pinfunction "1_1") (pintype "passive"))
      (node (ref "C24") (pin "1") (pinfunction "1_1") (pintype "passive"))
      (node (ref "C25") (pin "1") (pinfunction "1_1") (pintype "passive"))
      (node (ref "C8") (pin "1") (pinfunction "1_1") (pintype "passive"))
      (node (ref "C9") (pin "1") (pinfunction "1_1") (pintype "passive"))
      (node (ref "J2") (pin "1") (pintype "passive"))
      (node (ref "R10") (pin "2") (pinfunction "2_2") (pintype "passive"))
      (node (ref "R11") (pin "2") (pinfunction "2_2") (pintype "passive"))
      (node (ref "R18") (pin "2") (pinfunction "2_2") (pintype "passive"))
      (node (ref "R7") (pin "2") (pinfunction "2_2") (pintype "passive"))
      (node (ref "R8") (pin "2") (pinfunction "2_2") (pintype "passive"))
      (node (ref "R9") (pin "2") (pinfunction "2_2") (pintype "passive"))
      (node (ref "U2") (pin "1") (pinfunction "VDDANA_1") (pintype "power_in"))
      (node (ref "U2") (pin "2") (pinfunction "ADVREF_2") (pintype "input"))
      (node (ref "U2") (pin "22") (pinfunction "VDDIO_22") (pintype "power_in"))
      (node (ref "U2") (pin "36") (pinfunction "VDDIO_36") (pintype "power_in"))
      (node (ref "U2") (pin "4") (pinfunction "AD12BVREF_4") (pintype "bidirectional"))
      (node (ref "U2") (pin "42") (pinfunction "FWUP_42") (pintype "input"))
      (node (ref "U2") (pin "45") (pinfunction "VDDBU_45") (pintype "power_in"))
      (node (ref "U2") (pin "53") (pinfunction "VDDIN_53") (pintype "power_in"))
      (node (ref "U2") (pin "60") (pinfunction "VDDIO_60") (pintype "power_in"))
      (node (ref "U2") (pin "79") (pinfunction "VDDUTMI_79") (pintype "power_in"))
      (node (ref "U2") (pin "88") (pinfunction "VDDIO_88") (pintype "power_in"))
      (node (ref "U2") (pin "92") (pinfunction "PWMH2/A4/PB2_92") (pintype "bidirectional"))
    )
    (net (code "56") (name "unconnected-(J2-Pad7)") (class "Default")
      (node (ref "J2") (pin "7") (pintype "passive"))
    )
    (net (code "57") (name "unconnected-(J2-Pad9)") (class "Default")
      (node (ref "J2") (pin "9") (pintype "passive"))
    )
    (net (code "58") (name "unconnected-(J3-KEY-Pad7)") (class "Default")
      (node (ref "J3") (pin "7") (pinfunction "KEY_7") (pintype "passive"))
    )
    (net (code "59") (name "unconnected-(J3-TDI-Pad8)") (class "Default")
      (node (ref "J3") (pin "8") (pinfunction "TDI_8") (pintype "passive"))
    )
    (net (code "60") (name "unconnected-(SW5-T1-Pad1)") (class "Default")
      (node (ref "SW5") (pin "1") (pinfunction "T1_1") (pintype "passive"))
    )
    (net (code "61") (name "unconnected-(U2-A21(NANDALE{slash}RTS2{slash}PB21-Pad64)") (class "Default")
      (node (ref "U2") (pin "64") (pinfunction "A21(NANDALE/RTS2/PB21_64") (pintype "bidirectional"))
    )
    (net (code "62") (name "unconnected-(U2-A22{slash}NANDCLE{slash}CTS2{slash}PB22-Pad63)") (class "Default")
      (node (ref "U2") (pin "63") (pinfunction "A22/NANDCLE/CTS2/PB22_63") (pintype "bidirectional"))
    )
    (net (code "63") (name "unconnected-(U2-CTS0{slash}A1{slash}AD3{slash}PB8-Pad100)") (class "Default")
      (node (ref "U2") (pin "100") (pinfunction "CTS0/A1/AD3/PB8_100") (pintype "bidirectional"))
    )
    (net (code "64") (name "unconnected-(U2-D2{slash}DCD0{slash}PB11-Pad93)") (class "Default")
      (node (ref "U2") (pin "93") (pinfunction "D2/DCD0/PB11_93") (pintype "bidirectional"))
    )
    (net (code "65") (name "unconnected-(U2-D3{slash}RI0{slash}PB12-Pad94)") (class "Default")
      (node (ref "U2") (pin "94") (pinfunction "D3/RI0/PB12_94") (pintype "bidirectional"))
    )
    (net (code "66") (name "unconnected-(U2-D4{slash}PWMH0{slash}PB13-Pad95)") (class "Default")
      (node (ref "U2") (pin "95") (pinfunction "D4/PWMH0/PB13_95") (pintype "bidirectional"))
    )
    (net (code "67") (name "unconnected-(U2-D5{slash}PWMH1{slash}PB14-Pad69)") (class "Default")
      (node (ref "U2") (pin "69") (pinfunction "D5/PWMH1/PB14_69") (pintype "bidirectional"))
    )
    (net (code "68") (name "unconnected-(U2-JTAGSEL-Pad48)") (class "Default")
      (node (ref "U2") (pin "48") (pinfunction "JTAGSEL_48") (pintype "input+no_connect"))
    )
    (net (code "69") (name "unconnected-(U2-NANDRDY{slash}PCK1{slash}PB24-Pad58)") (class "Default")
      (node (ref "U2") (pin "58") (pinfunction "NANDRDY/PCK1/PB24_58") (pintype "bidirectional"))
    )
    (net (code "70") (name "unconnected-(U2-NCS0{slash}PWML3{slash}PB20-Pad65)") (class "Default")
      (node (ref "U2") (pin "65") (pinfunction "NCS0/PWML3/PB20_65") (pintype "bidirectional"))
    )
    (net (code "71") (name "unconnected-(U2-NRD{slash}PWML2{slash}PB19-Pad66)") (class "Default")
      (node (ref "U2") (pin "66") (pinfunction "NRD/PWML2/PB19_66") (pintype "bidirectional"))
    )
    (net (code "72") (name "unconnected-(U2-NWR0{slash}NWE{slash}PCK2{slash}PB23-Pad62)") (class "Default")
      (node (ref "U2") (pin "62") (pinfunction "NWR0/NWE/PCK2/PB23_62") (pintype "bidirectional"))
    )
    (net (code "73") (name "unconnected-(U2-PA0{slash}TIOB0{slash}NPCS1-Pad26)") (class "Default")
      (node (ref "U2") (pin "26") (pinfunction "PA0/TIOB0/NPCS1_26") (pintype "bidirectional"))
    )
    (net (code "74") (name "unconnected-(U2-PA2{slash}TCLK0{slash}AD12BTRG-Pad28)") (class "Default")
      (node (ref "U2") (pin "28") (pinfunction "PA2/TCLK0/AD12BTRG_28") (pintype "bidirectional"))
    )
    (net (code "75") (name "unconnected-(U2-PA3{slash}MCCK{slash}PCK1-Pad29)") (class "Default")
      (node (ref "U2") (pin "29") (pinfunction "PA3/MCCK/PCK1_29") (pintype "bidirectional"))
    )
    (net (code "76") (name "unconnected-(U2-PA4{slash}MCCDA{slash}PWMH0-Pad30)") (class "Default")
      (node (ref "U2") (pin "30") (pinfunction "PA4/MCCDA/PWMH0_30") (pintype "bidirectional"))
    )
    (net (code "77") (name "unconnected-(U2-PA5{slash}MCDA0{slash}PWMH1-Pad31)") (class "Default")
      (node (ref "U2") (pin "31") (pinfunction "PA5/MCDA0/PWMH1_31") (pintype "bidirectional"))
    )
    (net (code "78") (name "unconnected-(U2-PA8{slash}MCDA3{slash}PWML1-Pad37)") (class "Default")
      (node (ref "U2") (pin "37") (pinfunction "PA8/MCDA3/PWML1_37") (pintype "bidirectional"))
    )
    (net (code "79") (name "unconnected-(U2-PA13{slash}MISO-Pad10)") (class "Default")
      (node (ref "U2") (pin "10") (pinfunction "PA13/MISO_10") (pintype "bidirectional"))
    )
    (net (code "80") (name "unconnected-(U2-PA14{slash}MOSI-Pad11)") (class "Default")
      (node (ref "U2") (pin "11") (pinfunction "PA14/MOSI_11") (pintype "bidirectional"))
    )
    (net (code "81") (name "unconnected-(U2-PA16{slash}NPCS0{slash}NCS1-Pad13)") (class "Default")
      (node (ref "U2") (pin "13") (pinfunction "PA16/NPCS0/NCS1_13") (pintype "bidirectional"))
    )
    (net (code "82") (name "unconnected-(U2-PA20{slash}TXD1{slash}PWMH3-Pad19)") (class "Default")
      (node (ref "U2") (pin "19") (pinfunction "PA20/TXD1/PWMH3_19") (pintype "bidirectional"))
    )
    (net (code "83") (name "unconnected-(U2-PA23{slash}RXD2{slash}CTS1-Pad21)") (class "Default")
      (node (ref "U2") (pin "21") (pinfunction "PA23/RXD2/CTS1_21") (pintype "bidirectional"))
    )
    (net (code "84") (name "unconnected-(U2-PB4{slash}TCLK1{slash}A6{slash}AD12BAB3-Pad8)") (class "Default")
      (node (ref "U2") (pin "8") (pinfunction "PB4/TCLK1/A6/AD12BAB3_8") (pintype "bidirectional"))
    )
    (net (code "85") (name "unconnected-(U2-PB15{slash}D6{slash}PWMH2-Pad16)") (class "Default")
      (node (ref "U2") (pin "16") (pinfunction "PB15/D6/PWMH2_16") (pintype "bidirectional"))
    )
    (net (code "86") (name "unconnected-(U2-PB16{slash}D7{slash}PWMH3-Pad15)") (class "Default")
      (node (ref "U2") (pin "15") (pinfunction "PB16/D7/PWMH3_15") (pintype "bidirectional"))
    )
    (net (code "87") (name "unconnected-(U2-RD{slash}PCK0{slash}PA27-Pad96)") (class "Default")
      (node (ref "U2") (pin "96") (pinfunction "RD/PCK0/PA27_96") (pintype "bidirectional"))
    )
    (net (code "88") (name "unconnected-(U2-RF{slash}TIOB2{slash}PA31-Pad86)") (class "Default")
      (node (ref "U2") (pin "86") (pinfunction "RF/TIOB2/PA31_86") (pintype "bidirectional"))
    )
    (net (code "89") (name "unconnected-(U2-RTS0{slash}A0{slash}NBS0{slash}AD2{slash}PB7-Pad99)") (class "Default")
      (node (ref "U2") (pin "99") (pinfunction "RTS0/A0/NBS0/AD2/PB7_99") (pintype "bidirectional"))
    )
    (net (code "90") (name "unconnected-(U2-TEST-Pad44)") (class "Default")
      (node (ref "U2") (pin "44") (pinfunction "TEST_44") (pintype "input+no_connect"))
    )
    (net (code "91") (name "unconnected-(U2-XIN32-Pad50)") (class "Default")
      (node (ref "U2") (pin "50") (pinfunction "XIN32_50") (pintype "input+no_connect"))
    )
    (net (code "92") (name "unconnected-(U2-XOUT32-Pad49)") (class "Default")
      (node (ref "U2") (pin "49") (pinfunction "XOUT32_49") (pintype "output"))
    )
  )
)
